# Ponte_H_L293E.net
KiCad netlist of a schematic drawn in EAGLE
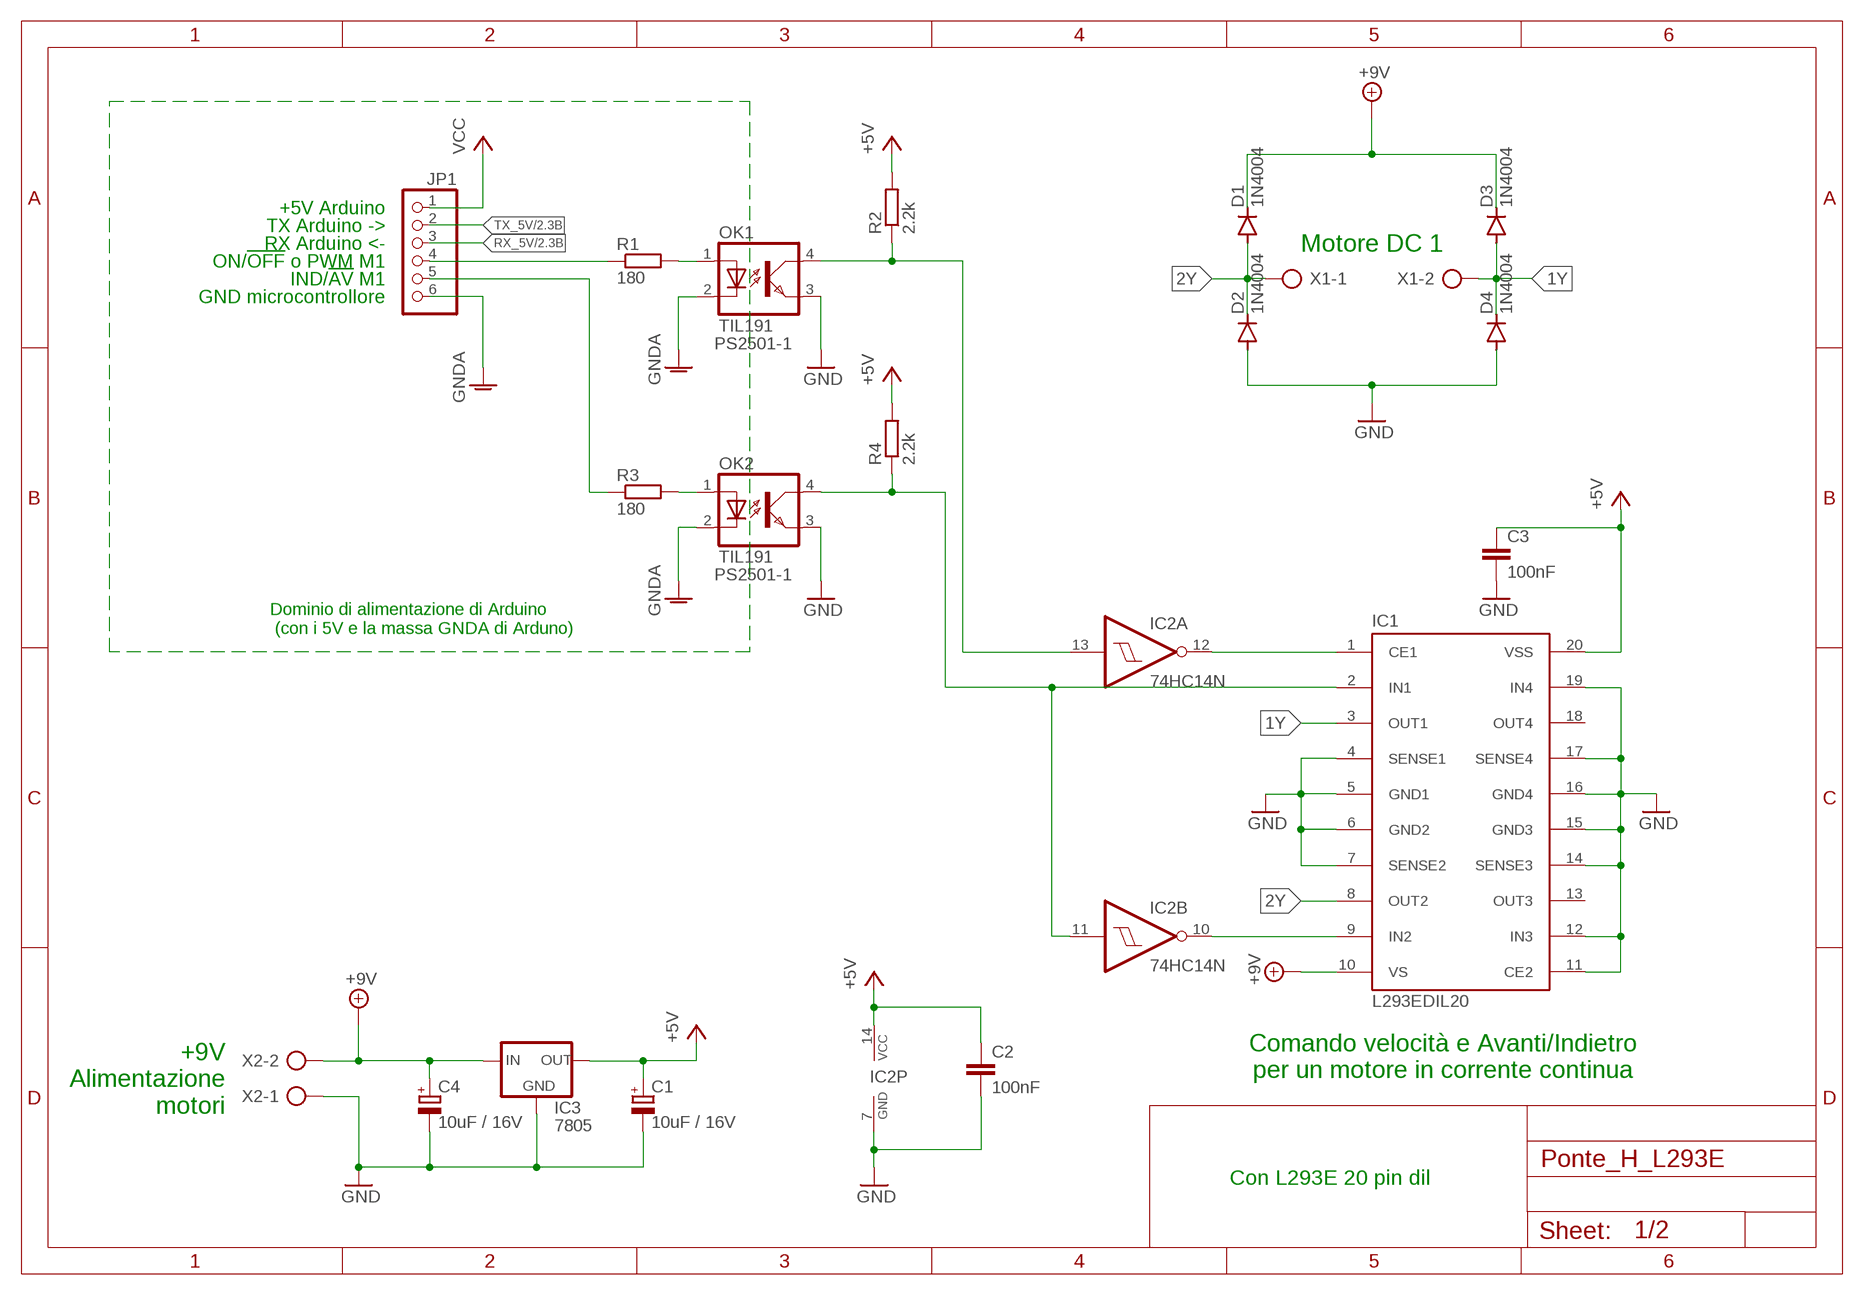
[diagram p0: schematic, sheet 1]
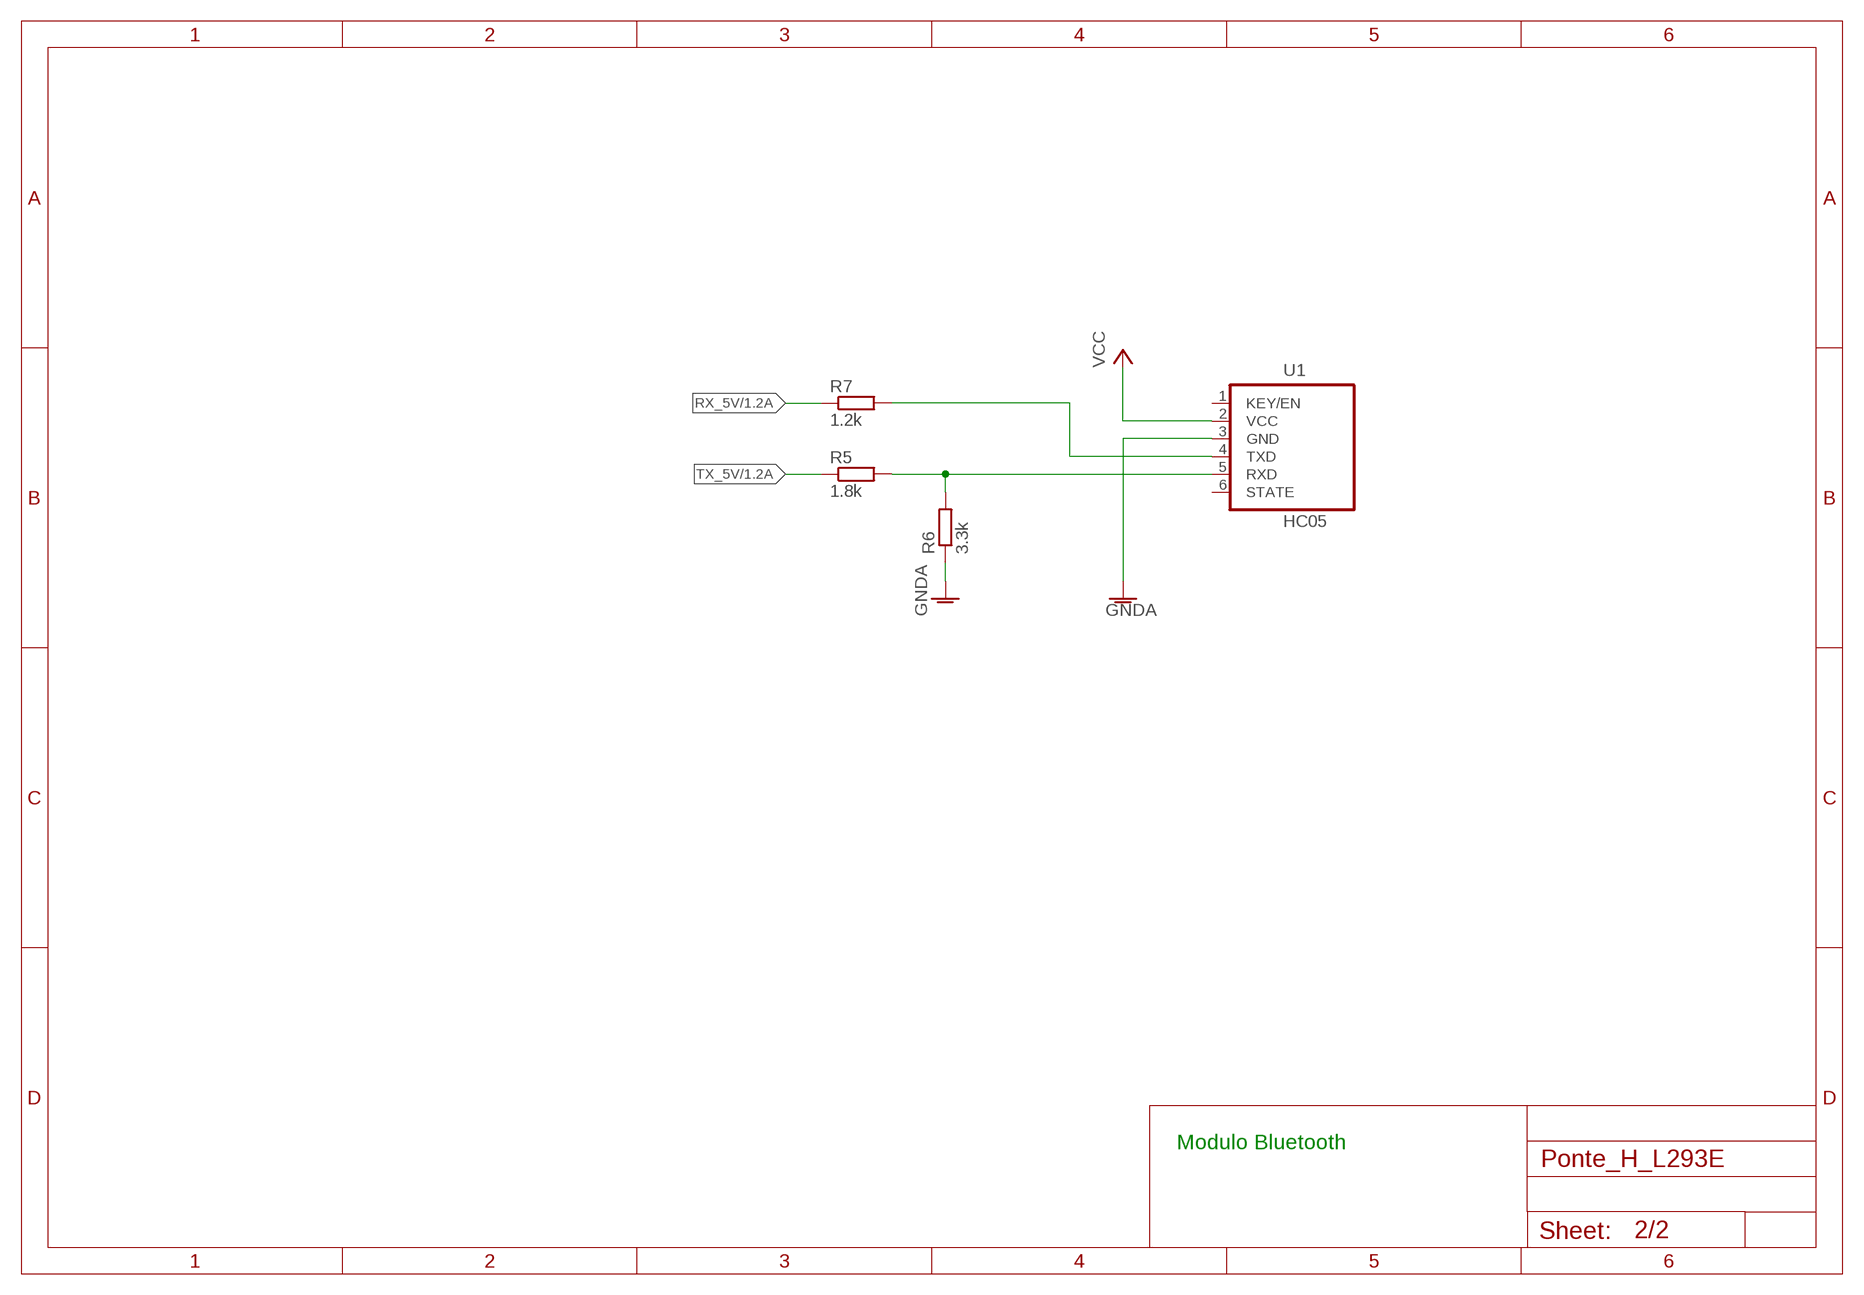
[diagram p1: schematic, sheet 2]

(export (version "E")
  (design (tool "Eeschema 10.0.6"))
  (components
    (comp (ref "C1")
      (value "10uF / 16V")
      (footprint "eagle-import:E5-8,5")
      (libsource (lib "eagle-import") (part "CPOL-EUE5-8.5"))
    )
    (comp (ref "C2")
      (value "100nF")
      (footprint "eagle-import:C050-025X075")
      (libsource (lib "eagle-import") (part "C-EU050-025X075"))
    )
    (comp (ref "C3")
      (value "100nF")
      (footprint "eagle-import:C050-025X075")
      (libsource (lib "eagle-import") (part "C-EU050-025X075"))
    )
    (comp (ref "C4")
      (value "10uF / 16V")
      (footprint "eagle-import:E5-8,5")
      (libsource (lib "eagle-import") (part "CPOL-EUE5-8.5"))
    )
    (comp (ref "D1")
      (value "1N4004")
      (footprint "eagle-import:DO41-10")
      (libsource (lib "eagle-import") (part "1N4004"))
    )
    (comp (ref "D2")
      (value "1N4004")
      (footprint "eagle-import:DO41-10")
      (libsource (lib "eagle-import") (part "1N4004"))
    )
    (comp (ref "D3")
      (value "1N4004")
      (footprint "eagle-import:DO41-10")
      (libsource (lib "eagle-import") (part "1N4004"))
    )
    (comp (ref "D4")
      (value "1N4004")
      (footprint "eagle-import:DO41-10")
      (libsource (lib "eagle-import") (part "1N4004"))
    )
    (comp (ref "IC1")
      (value "L293EDIL20")
      (footprint "eagle-import:DIL20")
      (libsource (lib "eagle-import") (part "L293EDIL20"))
    )
    (comp (ref "IC2")
      (value "74HC14N")
      (footprint "eagle-import:DIL14")
      (libsource (lib "eagle-import") (part "7414NHC"))
    )
    (comp (ref "IC3")
      (value "7805")
      (footprint "eagle-import:78XXS")
      (libsource (lib "eagle-import") (part "78XXS"))
    )
    (comp (ref "JP1")
      (value "PINHD-1X6")
      (footprint "eagle-import:1X06")
      (libsource (lib "eagle-import") (part "PINHD-1X6"))
    )
    (comp (ref "OK1")
      (value "TIL191")
      (footprint "eagle-import:DIL04")
      (fields (field (name "ALT") "PS2501-1"))
      (libsource (lib "eagle-import") (part "TIL191"))
    )
    (comp (ref "OK2")
      (value "TIL191")
      (footprint "eagle-import:DIL04")
      (fields (field (name "ALT") "PS2501-1"))
      (libsource (lib "eagle-import") (part "TIL191"))
    )
    (comp (ref "R1")
      (value "180")
      (footprint "eagle-import:0207_10")
      (libsource (lib "eagle-import") (part "R-EU_0207/10"))
    )
    (comp (ref "R2")
      (value "2.2k")
      (footprint "eagle-import:0207_10")
      (libsource (lib "eagle-import") (part "R-EU_0207/10"))
    )
    (comp (ref "R3")
      (value "180")
      (footprint "eagle-import:0207_10")
      (libsource (lib "eagle-import") (part "R-EU_0207/10"))
    )
    (comp (ref "R4")
      (value "2.2k")
      (footprint "eagle-import:0207_10")
      (libsource (lib "eagle-import") (part "R-EU_0207/10"))
    )
    (comp (ref "X1")
      (value "AK500/2")
      (footprint "eagle-import:AK500_2")
      (libsource (lib "eagle-import") (part "AK500/2"))
    )
    (comp (ref "X2")
      (value "AK500/2")
      (footprint "eagle-import:AK500_2")
      (libsource (lib "eagle-import") (part "AK500/2"))
    )
    (comp (ref "R5")
      (value "1.8k")
      (footprint "eagle-import:0207_10")
      (libsource (lib "eagle-import") (part "R-EU_0207/10"))
    )
    (comp (ref "R6")
      (value "3.3k")
      (footprint "eagle-import:0207_10")
      (libsource (lib "eagle-import") (part "R-EU_0207/10"))
    )
    (comp (ref "R7")
      (value "1.2k")
      (footprint "eagle-import:0207_10")
      (libsource (lib "eagle-import") (part "R-EU_0207/10"))
    )
    (comp (ref "U1")
      (value "HC05")
      (footprint "eagle-import:HC05-PIN")
      (libsource (lib "eagle-import") (part "HC05"))
    )
  )
  (nets
    (net (code "1") (name "+5V") (class "Default")
      (node (ref "C1") (pin "+") (pinfunction "+_+") (pintype "passive"))
      (node (ref "C2") (pin "1") (pinfunction "1_1") (pintype "passive"))
      (node (ref "C3") (pin "1") (pinfunction "1_1") (pintype "passive"))
      (node (ref "IC1") (pin "20") (pinfunction "VSS_20") (pintype "power_in"))
      (node (ref "IC2") (pin "14") (pinfunction "VCC_14") (pintype "power_in"))
      (node (ref "IC3") (pin "OUT") (pinfunction "OUT_OUT") (pintype "passive"))
      (node (ref "R2") (pin "2") (pinfunction "2_2") (pintype "passive"))
      (node (ref "R4") (pin "2") (pinfunction "2_2") (pintype "passive"))
    )
    (net (code "2") (name "+9V") (class "Default")
      (node (ref "C4") (pin "+") (pinfunction "+_+") (pintype "passive"))
      (node (ref "D1") (pin "C") (pinfunction "C_C") (pintype "passive"))
      (node (ref "D3") (pin "C") (pinfunction "C_C") (pintype "passive"))
      (node (ref "IC1") (pin "10") (pinfunction "VS_10") (pintype "power_in"))
      (node (ref "IC3") (pin "IN") (pinfunction "IN_IN") (pintype "input"))
      (node (ref "X2") (pin "2") (pinfunction "KL_2") (pintype "passive"))
    )
    (net (code "3") (name "1Y") (class "Default")
      (node (ref "D3") (pin "A") (pinfunction "A_A") (pintype "passive"))
      (node (ref "D4") (pin "C") (pinfunction "C_C") (pintype "passive"))
      (node (ref "IC1") (pin "3") (pinfunction "OUT1_3") (pintype "output"))
      (node (ref "X1") (pin "2") (pinfunction "KL_2") (pintype "passive"))
    )
    (net (code "4") (name "2Y") (class "Default")
      (node (ref "D1") (pin "A") (pinfunction "A_A") (pintype "passive"))
      (node (ref "D2") (pin "C") (pinfunction "C_C") (pintype "passive"))
      (node (ref "IC1") (pin "8") (pinfunction "OUT2_8") (pintype "output"))
      (node (ref "X1") (pin "1") (pinfunction "KL_1") (pintype "passive"))
    )
    (net (code "5") (name "GND") (class "Default")
      (node (ref "C1") (pin "-") (pinfunction "-_-") (pintype "passive"))
      (node (ref "C2") (pin "2") (pinfunction "2_2") (pintype "passive"))
      (node (ref "C3") (pin "2") (pinfunction "2_2") (pintype "passive"))
      (node (ref "C4") (pin "-") (pinfunction "-_-") (pintype "passive"))
      (node (ref "D2") (pin "A") (pinfunction "A_A") (pintype "passive"))
      (node (ref "D4") (pin "A") (pinfunction "A_A") (pintype "passive"))
      (node (ref "IC1") (pin "11") (pinfunction "CE2_11") (pintype "input"))
      (node (ref "IC1") (pin "12") (pinfunction "IN3_12") (pintype "input"))
      (node (ref "IC1") (pin "14") (pinfunction "SENSE3_14") (pintype "bidirectional"))
      (node (ref "IC1") (pin "15") (pinfunction "GND3_15") (pintype "power_in"))
      (node (ref "IC1") (pin "16") (pinfunction "GND4_16") (pintype "power_in"))
      (node (ref "IC1") (pin "17") (pinfunction "SENSE4_17") (pintype "bidirectional"))
      (node (ref "IC1") (pin "19") (pinfunction "IN4_19") (pintype "input"))
      (node (ref "IC1") (pin "4") (pinfunction "SENSE1_4") (pintype "bidirectional"))
      (node (ref "IC1") (pin "5") (pinfunction "GND1_5") (pintype "power_in"))
      (node (ref "IC1") (pin "6") (pinfunction "GND2_6") (pintype "power_in"))
      (node (ref "IC1") (pin "7") (pinfunction "SENSE2_7") (pintype "bidirectional"))
      (node (ref "IC2") (pin "7") (pinfunction "GND_7") (pintype "power_in"))
      (node (ref "IC3") (pin "GND") (pinfunction "GND_GND") (pintype "input"))
      (node (ref "OK1") (pin "3") (pinfunction "EMIT_3") (pintype "passive"))
      (node (ref "OK2") (pin "3") (pinfunction "EMIT_3") (pintype "passive"))
      (node (ref "X2") (pin "1") (pinfunction "KL_1") (pintype "passive"))
    )
    (net (code "6") (name "GNDA") (class "Default")
      (node (ref "JP1") (pin "6") (pinfunction "6_6") (pintype "passive"))
      (node (ref "OK1") (pin "2") (pinfunction "C_2") (pintype "passive"))
      (node (ref "OK2") (pin "2") (pinfunction "C_2") (pintype "passive"))
      (node (ref "R6") (pin "1") (pinfunction "1_1") (pintype "passive"))
      (node (ref "U1") (pin "3") (pinfunction "GND_3") (pintype "power_in"))
    )
    (net (code "7") (name "Net-(IC1-CE1)") (class "Default")
      (node (ref "IC1") (pin "1") (pinfunction "CE1_1") (pintype "input"))
      (node (ref "IC2") (pin "12") (pinfunction "O_12") (pintype "output"))
    )
    (net (code "8") (name "Net-(IC1-IN1)") (class "Default")
      (node (ref "IC1") (pin "2") (pinfunction "IN1_2") (pintype "input"))
      (node (ref "IC2") (pin "11") (pinfunction "I_11") (pintype "input"))
      (node (ref "OK2") (pin "4") (pinfunction "COL_4") (pintype "passive"))
      (node (ref "R4") (pin "1") (pinfunction "1_1") (pintype "passive"))
    )
    (net (code "9") (name "Net-(IC1-IN2)") (class "Default")
      (node (ref "IC1") (pin "9") (pinfunction "IN2_9") (pintype "input"))
      (node (ref "IC2") (pin "10") (pinfunction "O_10") (pintype "output"))
    )
    (net (code "10") (name "Net-(IC2A-I)") (class "Default")
      (node (ref "IC2") (pin "13") (pinfunction "I_13") (pintype "input"))
      (node (ref "OK1") (pin "4") (pinfunction "COL_4") (pintype "passive"))
      (node (ref "R2") (pin "1") (pinfunction "1_1") (pintype "passive"))
    )
    (net (code "11") (name "Net-(JP1-Pad4)") (class "Default")
      (node (ref "JP1") (pin "4") (pinfunction "4_4") (pintype "passive"))
      (node (ref "R1") (pin "1") (pinfunction "1_1") (pintype "passive"))
    )
    (net (code "12") (name "Net-(JP1-Pad5)") (class "Default")
      (node (ref "JP1") (pin "5") (pinfunction "5_5") (pintype "passive"))
      (node (ref "R3") (pin "1") (pinfunction "1_1") (pintype "passive"))
    )
    (net (code "13") (name "Net-(OK1-A)") (class "Default")
      (node (ref "OK1") (pin "1") (pinfunction "A_1") (pintype "passive"))
      (node (ref "R1") (pin "2") (pinfunction "2_2") (pintype "passive"))
    )
    (net (code "14") (name "Net-(OK2-A)") (class "Default")
      (node (ref "OK2") (pin "1") (pinfunction "A_1") (pintype "passive"))
      (node (ref "R3") (pin "2") (pinfunction "2_2") (pintype "passive"))
    )
    (net (code "15") (name "Net-(U1-RXD)") (class "Default")
      (node (ref "R5") (pin "2") (pinfunction "2_2") (pintype "passive"))
      (node (ref "R6") (pin "2") (pinfunction "2_2") (pintype "passive"))
      (node (ref "U1") (pin "5") (pinfunction "RXD_5") (pintype "input"))
    )
    (net (code "16") (name "Net-(U1-TXD)") (class "Default")
      (node (ref "R7") (pin "2") (pinfunction "2_2") (pintype "passive"))
      (node (ref "U1") (pin "4") (pinfunction "TXD_4") (pintype "output"))
    )
    (net (code "17") (name "RX_5V") (class "Default")
      (node (ref "JP1") (pin "3") (pinfunction "3_3") (pintype "passive"))
      (node (ref "R7") (pin "1") (pinfunction "1_1") (pintype "passive"))
    )
    (net (code "18") (name "TX_5V") (class "Default")
      (node (ref "JP1") (pin "2") (pinfunction "2_2") (pintype "passive"))
      (node (ref "R5") (pin "1") (pinfunction "1_1") (pintype "passive"))
    )
    (net (code "19") (name "VCC") (class "Default")
      (node (ref "JP1") (pin "1") (pinfunction "1_1") (pintype "passive"))
      (node (ref "U1") (pin "2") (pinfunction "VCC_2") (pintype "power_in"))
    )
    (net (code "20") (name "unconnected-(IC1-OUT3-Pad13)") (class "Default")
      (node (ref "IC1") (pin "13") (pinfunction "OUT3_13") (pintype "output"))
    )
    (net (code "21") (name "unconnected-(IC1-OUT4-Pad18)") (class "Default")
      (node (ref "IC1") (pin "18") (pinfunction "OUT4_18") (pintype "output"))
    )
    (net (code "22") (name "unconnected-(U1-KEY{slash}EN-Pad1)") (class "Default")
      (node (ref "U1") (pin "1") (pinfunction "KEY/EN_1") (pintype "input"))
    )
    (net (code "23") (name "unconnected-(U1-STATE-Pad6)") (class "Default")
      (node (ref "U1") (pin "6") (pinfunction "STATE_6") (pintype "output"))
    )
  )
)
